# usain_bot_chasis.net
KiCad netlist of a schematic drawn in EAGLE
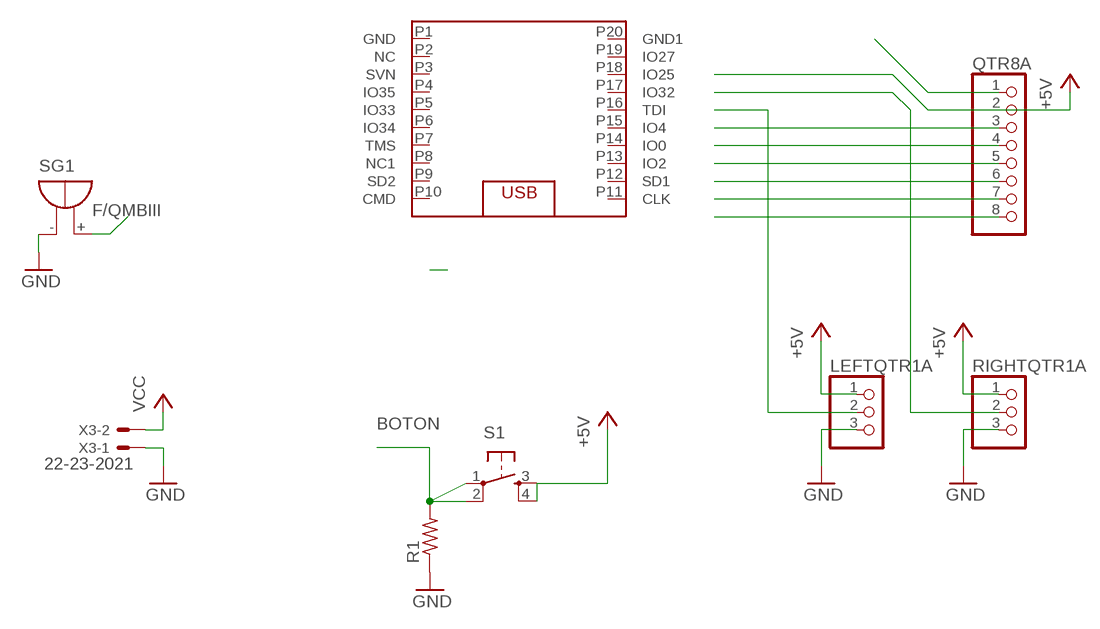
[diagram p0: schematic, sheet 1]

(export (version "E")
  (design (tool "Eeschema 10.0.6"))
  (components
    (comp (ref "ESP32")
      (value "ESP32_MINI_KIT")
      (footprint "eagle-import:ESP32_MINI_KIT")
      (libsource (lib "eagle-import") (part "ESP32_MINI_KIT"))
    )
    (comp (ref "LEFTQTR1A")
      (value "PINHD-1X3")
      (footprint "eagle-import:1X03")
      (libsource (lib "eagle-import") (part "PINHD-1X3"))
    )
    (comp (ref "QTR8A")
      (value "PINHD-1X8BIG")
      (footprint "eagle-import:1X08-BIG")
      (libsource (lib "eagle-import") (part "PINHD-1X8BIG"))
    )
    (comp (ref "R1")
      (value "R-US_0207/7")
      (footprint "eagle-import:0207_7")
      (libsource (lib "eagle-import") (part "R-US_0207/7"))
    )
    (comp (ref "RIGHTQTR1A")
      (value "PINHD-1X3")
      (footprint "eagle-import:1X03")
      (libsource (lib "eagle-import") (part "PINHD-1X3"))
    )
    (comp (ref "S1")
      (value "TAC_SWITCHPTH")
      (footprint "eagle-import:TACTILE-PTH")
      (libsource (lib "eagle-import") (part "TAC_SWITCHPTH"))
    )
    (comp (ref "SG1")
      (value "F/QMBIII")
      (footprint "eagle-import:F_QMBIII")
      (libsource (lib "eagle-import") (part "F/QMBIII"))
    )
    (comp (ref "X3")
      (value "22-23-2021")
      (footprint "eagle-import:22-23-2021")
      (fields (field (name "MF") "MOLEX"))
      (libsource (lib "eagle-import") (part "22-23-2021"))
    )
  )
  (nets
    (net (code "1") (name "+5V") (class "Default")
      (node (ref "LEFTQTR1A") (pin "1") (pinfunction "1_1") (pintype "passive"))
      (node (ref "QTR8A") (pin "2") (pinfunction "2_2") (pintype "passive"))
      (node (ref "RIGHTQTR1A") (pin "1") (pinfunction "1_1") (pintype "passive"))
      (node (ref "S1") (pin "3") (pinfunction "3_3") (pintype "passive"))
      (node (ref "S1") (pin "4") (pinfunction "4_4") (pintype "passive"))
    )
    (net (code "2") (name "/BOTON") (class "Default")
      (node (ref "R1") (pin "2") (pinfunction "2_2") (pintype "passive"))
      (node (ref "S1") (pin "1") (pinfunction "1_1") (pintype "passive"))
      (node (ref "S1") (pin "2") (pinfunction "2_2") (pintype "passive"))
    )
    (net (code "3") (name "GND") (class "Default")
      (node (ref "LEFTQTR1A") (pin "3") (pinfunction "3_3") (pintype "passive"))
      (node (ref "R1") (pin "1") (pinfunction "1_1") (pintype "passive"))
      (node (ref "RIGHTQTR1A") (pin "3") (pinfunction "3_3") (pintype "passive"))
      (node (ref "SG1") (pin "-") (pinfunction "+_-") (pintype "passive"))
      (node (ref "X3") (pin "1") (pinfunction "S_1") (pintype "passive"))
    )
    (net (code "4") (name "VCC") (class "Default")
      (node (ref "X3") (pin "2") (pinfunction "S_2") (pintype "passive"))
    )
    (net (code "5") (name "unconnected-(ESP32-CLK-PadP11)") (class "Default")
      (node (ref "ESP32") (pin "P11") (pinfunction "CLK_P11") (pintype "bidirectional"))
    )
    (net (code "6") (name "unconnected-(ESP32-CMD-PadP10)") (class "Default")
      (node (ref "ESP32") (pin "P10") (pinfunction "CMD_P10") (pintype "bidirectional"))
    )
    (net (code "7") (name "unconnected-(ESP32-GND-PadP1)") (class "Default")
      (node (ref "ESP32") (pin "P1") (pinfunction "GND_P1") (pintype "bidirectional"))
    )
    (net (code "8") (name "unconnected-(ESP32-GND1-PadP20)") (class "Default")
      (node (ref "ESP32") (pin "P20") (pinfunction "GND1_P20") (pintype "bidirectional"))
    )
    (net (code "9") (name "unconnected-(ESP32-IO0-PadP14)") (class "Default")
      (node (ref "ESP32") (pin "P14") (pinfunction "IO0_P14") (pintype "bidirectional"))
    )
    (net (code "10") (name "unconnected-(ESP32-IO2-PadP13)") (class "Default")
      (node (ref "ESP32") (pin "P13") (pinfunction "IO2_P13") (pintype "bidirectional"))
    )
    (net (code "11") (name "unconnected-(ESP32-IO4-PadP15)") (class "Default")
      (node (ref "ESP32") (pin "P15") (pinfunction "IO4_P15") (pintype "bidirectional"))
    )
    (net (code "12") (name "unconnected-(ESP32-IO25-PadP18)") (class "Default")
      (node (ref "ESP32") (pin "P18") (pinfunction "IO25_P18") (pintype "bidirectional"))
    )
    (net (code "13") (name "unconnected-(ESP32-IO27-PadP19)") (class "Default")
      (node (ref "ESP32") (pin "P19") (pinfunction "IO27_P19") (pintype "bidirectional"))
    )
    (net (code "14") (name "unconnected-(ESP32-IO32-PadP17)") (class "Default")
      (node (ref "ESP32") (pin "P17") (pinfunction "IO32_P17") (pintype "bidirectional"))
    )
    (net (code "15") (name "unconnected-(ESP32-IO33-PadP5)") (class "Default")
      (node (ref "ESP32") (pin "P5") (pinfunction "IO33_P5") (pintype "bidirectional"))
    )
    (net (code "16") (name "unconnected-(ESP32-IO34-PadP6)") (class "Default")
      (node (ref "ESP32") (pin "P6") (pinfunction "IO34_P6") (pintype "bidirectional"))
    )
    (net (code "17") (name "unconnected-(ESP32-IO35-PadP4)") (class "Default")
      (node (ref "ESP32") (pin "P4") (pinfunction "IO35_P4") (pintype "bidirectional"))
    )
    (net (code "18") (name "unconnected-(ESP32-NC-PadP2)") (class "Default")
      (node (ref "ESP32") (pin "P2") (pinfunction "NC_P2") (pintype "bidirectional"))
    )
    (net (code "19") (name "unconnected-(ESP32-NC1-PadP8)") (class "Default")
      (node (ref "ESP32") (pin "P8") (pinfunction "NC1_P8") (pintype "bidirectional"))
    )
    (net (code "20") (name "unconnected-(ESP32-SD1-PadP12)") (class "Default")
      (node (ref "ESP32") (pin "P12") (pinfunction "SD1_P12") (pintype "bidirectional"))
    )
    (net (code "21") (name "unconnected-(ESP32-SD2-PadP9)") (class "Default")
      (node (ref "ESP32") (pin "P9") (pinfunction "SD2_P9") (pintype "bidirectional"))
    )
    (net (code "22") (name "unconnected-(ESP32-SVN-PadP3)") (class "Default")
      (node (ref "ESP32") (pin "P3") (pinfunction "SVN_P3") (pintype "bidirectional"))
    )
    (net (code "23") (name "unconnected-(ESP32-TDI-PadP16)") (class "Default")
      (node (ref "ESP32") (pin "P16") (pinfunction "TDI_P16") (pintype "bidirectional"))
    )
    (net (code "24") (name "unconnected-(ESP32-TMS-PadP7)") (class "Default")
      (node (ref "ESP32") (pin "P7") (pinfunction "TMS_P7") (pintype "bidirectional"))
    )
    (net (code "25") (name "unconnected-(LEFTQTR1A-Pad2)") (class "Default")
      (node (ref "LEFTQTR1A") (pin "2") (pinfunction "2_2") (pintype "passive"))
    )
    (net (code "26") (name "unconnected-(QTR8A-Pad1)") (class "Default")
      (node (ref "QTR8A") (pin "1") (pinfunction "1_1") (pintype "passive"))
    )
    (net (code "27") (name "unconnected-(QTR8A-Pad3)") (class "Default")
      (node (ref "QTR8A") (pin "3") (pinfunction "3_3") (pintype "passive"))
    )
    (net (code "28") (name "unconnected-(QTR8A-Pad4)") (class "Default")
      (node (ref "QTR8A") (pin "4") (pinfunction "4_4") (pintype "passive"))
    )
    (net (code "29") (name "unconnected-(QTR8A-Pad5)") (class "Default")
      (node (ref "QTR8A") (pin "5") (pinfunction "5_5") (pintype "passive"))
    )
    (net (code "30") (name "unconnected-(QTR8A-Pad6)") (class "Default")
      (node (ref "QTR8A") (pin "6") (pinfunction "6_6") (pintype "passive"))
    )
    (net (code "31") (name "unconnected-(QTR8A-Pad7)") (class "Default")
      (node (ref "QTR8A") (pin "7") (pinfunction "7_7") (pintype "passive"))
    )
    (net (code "32") (name "unconnected-(QTR8A-Pad8)") (class "Default")
      (node (ref "QTR8A") (pin "8") (pinfunction "8_8") (pintype "passive"))
    )
    (net (code "33") (name "unconnected-(RIGHTQTR1A-Pad2)") (class "Default")
      (node (ref "RIGHTQTR1A") (pin "2") (pinfunction "2_2") (pintype "passive"))
    )
    (net (code "34") (name "unconnected-(SG1---Pad+)") (class "Default")
      (node (ref "SG1") (pin "+") (pinfunction "-_+") (pintype "passive"))
    )
  )
)
